# Sensor_Board.net
KiCad netlist of a schematic drawn in Altium Designer
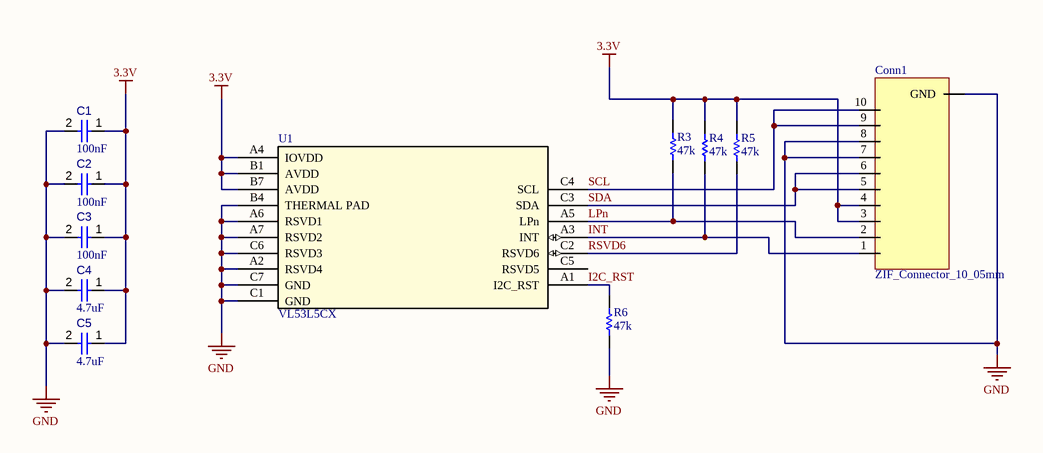
[diagram p0: Sensor_Board.SchDoc]

(export (version "E")
  (design (tool "Eeschema 10.0.6"))
  (components
    (comp (ref "C1")
      (value "100nF")
      (footprint "CAPC1608X90X40NL10T20")
      (description "Chip Capacitor, 100 nF, +/- 10%, 50 V, 0603 (1608 Metric)")
      (fields (field (name "TOLERANCE") "10%") (field (name "Comment") "Capacitor 100 nF +/-10% 50 V 0603"))
      (libsource (lib "Domen's Workpace") (part "CAP-NP-2"))
    )
    (comp (ref "C2")
      (value "100nF")
      (footprint "CAPC1608X90X40NL10T20")
      (description "Chip Capacitor, 100 nF, +/- 10%, 50 V, 0603 (1608 Metric)")
      (fields (field (name "TOLERANCE") "10%") (field (name "Comment") "Capacitor 100 nF +/-10% 50 V 0603"))
      (libsource (lib "Domen's Workpace") (part "CAP-NP-2"))
    )
    (comp (ref "C3")
      (value "100nF")
      (footprint "CAPC1608X90X40NL10T20")
      (description "Chip Capacitor, 100 nF, +/- 10%, 50 V, 0603 (1608 Metric)")
      (fields (field (name "TOLERANCE") "10%") (field (name "Comment") "Capacitor 100 nF +/-10% 50 V 0603"))
      (libsource (lib "Domen's Workpace") (part "CAP-NP-2"))
    )
    (comp (ref "C4")
      (value "4.7uF")
      (footprint "CAPC1608X90X40NL10T20")
      (description "Chip Capacitor, 100 nF, +/- 10%, 50 V, 0603 (1608 Metric)")
      (fields (field (name "TOLERANCE") "10%") (field (name "Comment") "Capacitor 100 nF +/-10% 50 V 0603"))
      (libsource (lib "Domen's Workpace") (part "CAP-NP-2"))
    )
    (comp (ref "C5")
      (value "4.7uF")
      (footprint "CAPC1608X90X40NL10T20")
      (description "Chip Capacitor, 100 nF, +/- 10%, 50 V, 0603 (1608 Metric)")
      (fields (field (name "TOLERANCE") "10%") (field (name "Comment") "Capacitor 100 nF +/-10% 50 V 0603"))
      (libsource (lib "Domen's Workpace") (part "CAP-NP-2"))
    )
    (comp (ref "Conn1")
      (value "ZIF_Connector_10_05mm")
      (footprint "ZIF_Connector_10_05mm")
      (libsource (lib "MainLib") (part "ZIF_Connector_10_05mm"))
    )
    (comp (ref "R3")
      (value "47k")
      (footprint "RESC1608X55X25NL10T15")
      (description "Chip Resistor, 0 Ohm, 0.1 W, -55 to 155 degC, 0603 (1608 Metric)")
      (fields (field (name "POWER") "100mW") (field (name "TOLERANCE") "5%"))
      (libsource (lib "Domen's Workpace") (part "RES-2"))
    )
    (comp (ref "R4")
      (value "47k")
      (footprint "RESC1608X55X25NL10T15")
      (description "Chip Resistor, 0 Ohm, 0.1 W, -55 to 155 degC, 0603 (1608 Metric)")
      (fields (field (name "POWER") "100mW") (field (name "TOLERANCE") "5%"))
      (libsource (lib "Domen's Workpace") (part "RES-2"))
    )
    (comp (ref "R5")
      (value "47k")
      (footprint "RESC1608X55X25NL10T15")
      (description "Chip Resistor, 0 Ohm, 0.1 W, -55 to 155 degC, 0603 (1608 Metric)")
      (fields (field (name "POWER") "100mW") (field (name "TOLERANCE") "5%"))
      (libsource (lib "Domen's Workpace") (part "RES-2"))
    )
    (comp (ref "R6")
      (value "47k")
      (footprint "RESC1608X55X25NL10T15")
      (description "Chip Resistor, 0 Ohm, 0.1 W, -55 to 155 degC, 0603 (1608 Metric)")
      (fields (field (name "POWER") "100mW") (field (name "TOLERANCE") "5%"))
      (libsource (lib "Domen's Workpace") (part "RES-2"))
    )
    (comp (ref "U1")
      (value "VL53L5CX")
      (footprint "vl53l5cx")
      (description "No Description Available")
      (fields
        (field (name "MANUFACTURER_PART_NUMBER") "VL53L5CXV0GC/1")
        (field (name "COPYRIGHT") "Copyright (C) 2022 Ultra Librarian. All rights reserved.")
      )
      (libsource (lib "MainLib") (part "VL53L5CX"))
    )
  )
  (nets
    (net (code "1") (name "/I2C_RST") (class "Default")
      (node (ref "R6") (pin "1") (pinfunction "1_1") (pintype "passive"))
      (node (ref "U1") (pin "A1") (pinfunction "I2C_RST_A1") (pintype "passive"))
    )
    (net (code "2") (name "/INT") (class "Default")
      (node (ref "Conn1") (pin "1") (pinfunction "1_1") (pintype "passive"))
      (node (ref "R4") (pin "2") (pinfunction "2_2") (pintype "passive"))
      (node (ref "U1") (pin "A3") (pinfunction "INT_A3") (pintype "bidirectional"))
    )
    (net (code "3") (name "/LPn") (class "Default")
      (node (ref "Conn1") (pin "2") (pinfunction "2_2") (pintype "passive"))
      (node (ref "R3") (pin "2") (pinfunction "2_2") (pintype "passive"))
      (node (ref "U1") (pin "A5") (pinfunction "LPn_A5") (pintype "passive"))
    )
    (net (code "4") (name "/RSVD6") (class "Default")
      (node (ref "R5") (pin "2") (pinfunction "2_2") (pintype "passive"))
      (node (ref "U1") (pin "C2") (pinfunction "RSVD6_C2") (pintype "bidirectional"))
    )
    (net (code "5") (name "/SCL") (class "Default")
      (node (ref "Conn1") (pin "10") (pinfunction "10_10") (pintype "passive"))
      (node (ref "Conn1") (pin "9") (pinfunction "9_9") (pintype "passive"))
      (node (ref "U1") (pin "C4") (pinfunction "SCL_C4") (pintype "passive"))
    )
    (net (code "6") (name "/SDA") (class "Default")
      (node (ref "Conn1") (pin "5") (pinfunction "5_5") (pintype "passive"))
      (node (ref "Conn1") (pin "6") (pinfunction "6_6") (pintype "passive"))
      (node (ref "U1") (pin "C3") (pinfunction "SDA_C3") (pintype "passive"))
    )
    (net (code "7") (name "3.3V") (class "Default")
      (node (ref "C1") (pin "1") (pinfunction "1_1") (pintype "passive"))
      (node (ref "C2") (pin "1") (pinfunction "1_1") (pintype "passive"))
      (node (ref "C3") (pin "1") (pinfunction "1_1") (pintype "passive"))
      (node (ref "C4") (pin "1") (pinfunction "1_1") (pintype "passive"))
      (node (ref "C5") (pin "1") (pinfunction "1_1") (pintype "passive"))
      (node (ref "Conn1") (pin "3") (pinfunction "3_3") (pintype "passive"))
      (node (ref "Conn1") (pin "4") (pinfunction "4_4") (pintype "passive"))
      (node (ref "R3") (pin "1") (pinfunction "1_1") (pintype "passive"))
      (node (ref "R4") (pin "1") (pinfunction "1_1") (pintype "passive"))
      (node (ref "R5") (pin "1") (pinfunction "1_1") (pintype "passive"))
      (node (ref "U1") (pin "A4") (pinfunction "IOVDD_A4") (pintype "power_in"))
      (node (ref "U1") (pin "B1") (pinfunction "AVDD_B1") (pintype "power_in"))
      (node (ref "U1") (pin "B7") (pinfunction "AVDD_B7") (pintype "power_in"))
    )
    (net (code "8") (name "GND") (class "Default")
      (node (ref "C1") (pin "2") (pinfunction "2_2") (pintype "passive"))
      (node (ref "C2") (pin "2") (pinfunction "2_2") (pintype "passive"))
      (node (ref "C3") (pin "2") (pinfunction "2_2") (pintype "passive"))
      (node (ref "C4") (pin "2") (pinfunction "2_2") (pintype "passive"))
      (node (ref "C5") (pin "2") (pinfunction "2_2") (pintype "passive"))
      (node (ref "Conn1") (pin "7") (pinfunction "7_7") (pintype "passive"))
      (node (ref "Conn1") (pin "8") (pinfunction "8_8") (pintype "passive"))
      (node (ref "Conn1") (pin "GND") (pinfunction "GND_GND") (pintype "passive"))
      (node (ref "R6") (pin "2") (pinfunction "2_2") (pintype "passive"))
      (node (ref "U1") (pin "A2") (pinfunction "RSVD4_A2") (pintype "passive"))
      (node (ref "U1") (pin "A6") (pinfunction "RSVD1_A6") (pintype "passive"))
      (node (ref "U1") (pin "A7") (pinfunction "RSVD2_A7") (pintype "passive"))
      (node (ref "U1") (pin "B4") (pinfunction "THERMAL_PAD_B4") (pintype "passive"))
      (node (ref "U1") (pin "C1") (pinfunction "GND_C1") (pintype "passive"))
      (node (ref "U1") (pin "C6") (pinfunction "RSVD3_C6") (pintype "passive"))
      (node (ref "U1") (pin "C7") (pinfunction "GND_C7") (pintype "passive"))
    )
    (net (code "9") (name "unconnected-(U1-RSVD5-PadC5)") (class "Default")
      (node (ref "U1") (pin "C5") (pinfunction "RSVD5_C5") (pintype "passive"))
    )
  )
)
